# SCA3100-D04_Breakout.net
KiCad netlist of a schematic drawn in EAGLE
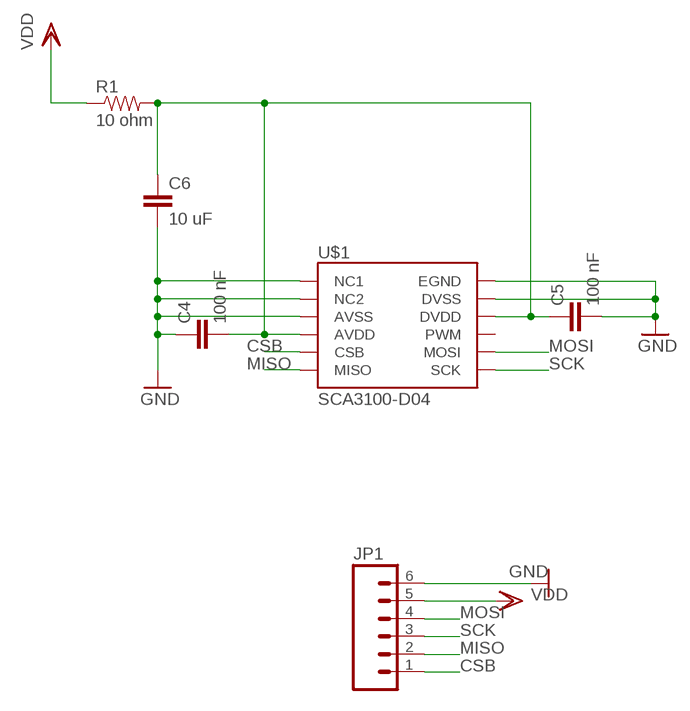
[diagram p0: schematic, sheet 1]

(export (version "E")
  (design (tool "Eeschema 10.0.6"))
  (components
    (comp (ref "C4")
      (value "100 nF")
      (footprint "eagle-import:0805")
      (libsource (lib "eagle-import") (part "CAP0805"))
    )
    (comp (ref "C5")
      (value "100 nF")
      (footprint "eagle-import:0805")
      (libsource (lib "eagle-import") (part "CAP0805"))
    )
    (comp (ref "C6")
      (value "10 uF")
      (footprint "eagle-import:0805")
      (libsource (lib "eagle-import") (part "CAP0805"))
    )
    (comp (ref "JP1")
      (value "M06")
      (footprint "eagle-import:1X06")
      (libsource (lib "eagle-import") (part "M06"))
    )
    (comp (ref "R1")
      (value "10 ohm")
      (footprint "eagle-import:0805")
      (libsource (lib "eagle-import") (part "RESISTOR0805-RES"))
    )
    (comp (ref "U$1")
      (value "SCA3100-D04")
      (footprint "eagle-import:SCA3100-D04")
      (libsource (lib "eagle-import") (part "SCA3100-D04"))
    )
  )
  (nets
    (net (code "1") (name "/CSB") (class "Default")
      (node (ref "JP1") (pin "1") (pinfunction "1_1") (pintype "passive"))
      (node (ref "U$1") (pin "CSB") (pinfunction "CSB_CSB") (pintype "bidirectional"))
    )
    (net (code "2") (name "/MISO") (class "Default")
      (node (ref "JP1") (pin "2") (pinfunction "2_2") (pintype "passive"))
      (node (ref "U$1") (pin "MISO") (pinfunction "MISO_MISO") (pintype "bidirectional"))
    )
    (net (code "3") (name "/MOSI") (class "Default")
      (node (ref "JP1") (pin "4") (pinfunction "4_4") (pintype "passive"))
      (node (ref "U$1") (pin "MOSI") (pinfunction "MOSI_MOSI") (pintype "bidirectional"))
    )
    (net (code "4") (name "/SCK") (class "Default")
      (node (ref "JP1") (pin "3") (pinfunction "3_3") (pintype "passive"))
      (node (ref "U$1") (pin "SCK") (pinfunction "SCK_SCK") (pintype "bidirectional"))
    )
    (net (code "5") (name "GND") (class "Default")
      (node (ref "C4") (pin "1") (pinfunction "1_1") (pintype "passive"))
      (node (ref "C5") (pin "2") (pinfunction "2_2") (pintype "passive"))
      (node (ref "C6") (pin "2") (pinfunction "2_2") (pintype "passive"))
      (node (ref "JP1") (pin "6") (pinfunction "6_6") (pintype "passive"))
      (node (ref "U$1") (pin "AVSS") (pinfunction "AVSS_AVSS") (pintype "bidirectional"))
      (node (ref "U$1") (pin "DVSS") (pinfunction "DVSS_DVSS") (pintype "bidirectional"))
      (node (ref "U$1") (pin "EGND") (pinfunction "EGND_EGND") (pintype "bidirectional"))
      (node (ref "U$1") (pin "NC1") (pinfunction "NC1_NC1") (pintype "bidirectional"))
      (node (ref "U$1") (pin "NC2") (pinfunction "NC2_NC2") (pintype "bidirectional"))
    )
    (net (code "6") (name "Net-(C4-Pad2)") (class "Default")
      (node (ref "C4") (pin "2") (pinfunction "2_2") (pintype "passive"))
      (node (ref "C5") (pin "1") (pinfunction "1_1") (pintype "passive"))
      (node (ref "C6") (pin "1") (pinfunction "1_1") (pintype "passive"))
      (node (ref "R1") (pin "2") (pinfunction "2_2") (pintype "passive"))
      (node (ref "U$1") (pin "AVDD") (pinfunction "AVDD_AVDD") (pintype "bidirectional"))
      (node (ref "U$1") (pin "DVDD") (pinfunction "DVDD_DVDD") (pintype "bidirectional"))
    )
    (net (code "7") (name "VDD") (class "Default")
      (node (ref "JP1") (pin "5") (pinfunction "5_5") (pintype "passive"))
      (node (ref "R1") (pin "1") (pinfunction "1_1") (pintype "passive"))
    )
    (net (code "8") (name "unconnected-(U$1-PadPWM)") (class "Default")
      (node (ref "U$1") (pin "PWM") (pinfunction "PWM_PWM") (pintype "bidirectional"))
    )
  )
)
